# Motor_Drivers.net
KiCad netlist of a schematic drawn in Altium Designer
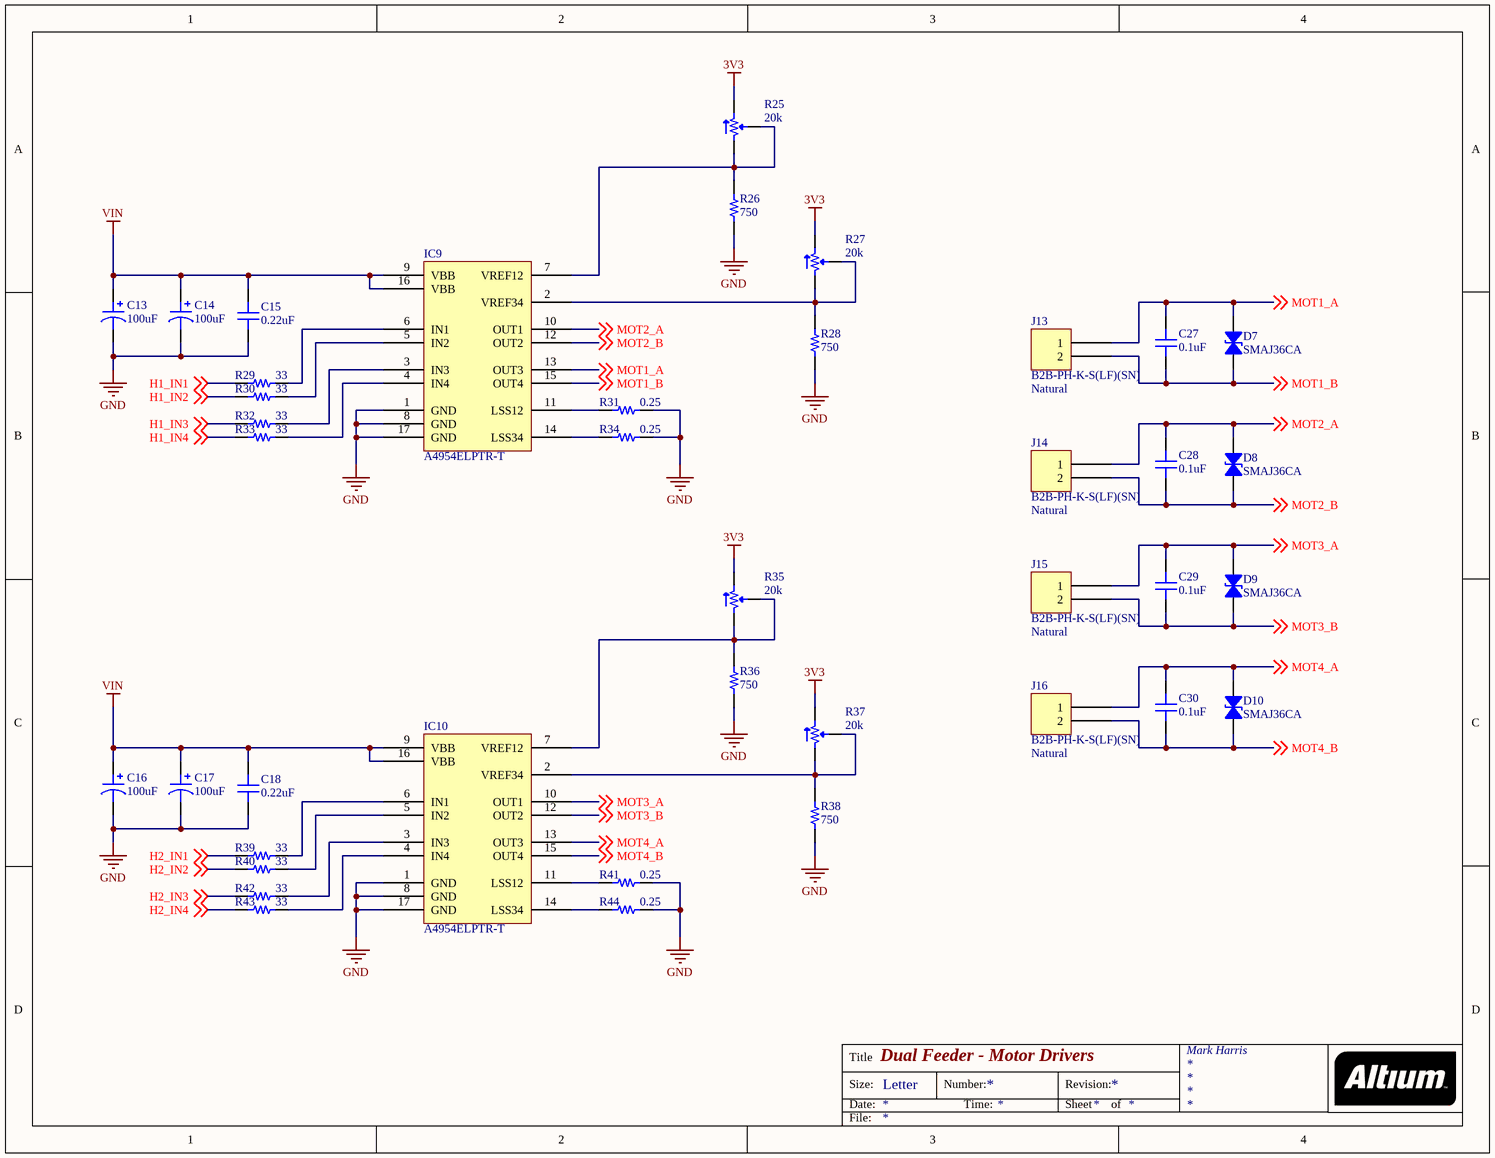
[diagram p0: Motor Drivers.SchDoc]

(export (version "E")
  (design (tool "Eeschema 10.0.6"))
  (components
    (comp (ref "C13")
      (value "100uF")
      (footprint "CAP ALUM 8.3MM")
      (description "CAP ALUM 100UF 20% 50V SMD")
      (fields (field (name "PART NUMBER") "UWT1H101MNL1GS") (field (name "MANUFACTURER") "Nichicon"))
      (libsource (lib "Celestial Library Database") (part "Polarised Capacitor"))
    )
    (comp (ref "C14")
      (value "100uF")
      (footprint "CAP ALUM 8.3MM")
      (description "CAP ALUM 100UF 20% 50V SMD")
      (fields (field (name "PART NUMBER") "UWT1H101MNL1GS") (field (name "MANUFACTURER") "Nichicon"))
      (libsource (lib "Celestial Library Database") (part "Polarised Capacitor"))
    )
    (comp (ref "C15")
      (value "0.22uF")
      (footprint "CAP 0805/2012")
      (description "CAP CER 0.22UF 50V X7R 0805")
      (fields
        (field (name "PART NUMBER") "CL21B224KBFSFNE")
        (field (name "MANUFACTURER") "Samsung Electro-Mechanics America, Inc.")
      )
      (libsource (lib "Celestial Library Database") (part "Capacitor"))
    )
    (comp (ref "C16")
      (value "100uF")
      (footprint "CAP ALUM 8.3MM")
      (description "CAP ALUM 100UF 20% 50V SMD")
      (fields (field (name "PART NUMBER") "UWT1H101MNL1GS") (field (name "MANUFACTURER") "Nichicon"))
      (libsource (lib "Celestial Library Database") (part "Polarised Capacitor"))
    )
    (comp (ref "C17")
      (value "100uF")
      (footprint "CAP ALUM 8.3MM")
      (description "CAP ALUM 100UF 20% 50V SMD")
      (fields (field (name "PART NUMBER") "UWT1H101MNL1GS") (field (name "MANUFACTURER") "Nichicon"))
      (libsource (lib "Celestial Library Database") (part "Polarised Capacitor"))
    )
    (comp (ref "C18")
      (value "0.22uF")
      (footprint "CAP 0805/2012")
      (description "CAP CER 0.22UF 50V X7R 0805")
      (fields
        (field (name "PART NUMBER") "CL21B224KBFSFNE")
        (field (name "MANUFACTURER") "Samsung Electro-Mechanics America, Inc.")
      )
      (libsource (lib "Celestial Library Database") (part "Capacitor"))
    )
    (comp (ref "C27")
      (value "0.1uF")
      (footprint "CAP 0603/1608")
      (description "CAP CER 0.1UF 50V X7R 0603")
      (fields
        (field (name "PART NUMBER") "CL10B104JB8NNNC")
        (field (name "MANUFACTURER") "Samsung Electro-Mechanics America, Inc.")
      )
      (libsource (lib "Celestial Library Database") (part "Capacitor"))
    )
    (comp (ref "C28")
      (value "0.1uF")
      (footprint "CAP 0603/1608")
      (description "CAP CER 0.1UF 50V X7R 0603")
      (fields
        (field (name "PART NUMBER") "CL10B104JB8NNNC")
        (field (name "MANUFACTURER") "Samsung Electro-Mechanics America, Inc.")
      )
      (libsource (lib "Celestial Library Database") (part "Capacitor"))
    )
    (comp (ref "C29")
      (value "0.1uF")
      (footprint "CAP 0603/1608")
      (description "CAP CER 0.1UF 50V X7R 0603")
      (fields
        (field (name "PART NUMBER") "CL10B104JB8NNNC")
        (field (name "MANUFACTURER") "Samsung Electro-Mechanics America, Inc.")
      )
      (libsource (lib "Celestial Library Database") (part "Capacitor"))
    )
    (comp (ref "C30")
      (value "0.1uF")
      (footprint "CAP 0603/1608")
      (description "CAP CER 0.1UF 50V X7R 0603")
      (fields
        (field (name "PART NUMBER") "CL10B104JB8NNNC")
        (field (name "MANUFACTURER") "Samsung Electro-Mechanics America, Inc.")
      )
      (libsource (lib "Celestial Library Database") (part "Capacitor"))
    )
    (comp (ref "D7")
      (value "SMAJ36CA")
      (footprint "Bourns DO214AC SMA")
      (description "TVS DIODE 36VWM 58.1VC DO214AC")
      (fields (field (name "MANUFACTURER") "Bourns Inc."))
      (libsource (lib "Celestial Library Database") (part "Diode Zener Bidirectional"))
    )
    (comp (ref "D8")
      (value "SMAJ36CA")
      (footprint "Bourns DO214AC SMA")
      (description "TVS DIODE 36VWM 58.1VC DO214AC")
      (fields (field (name "MANUFACTURER") "Bourns Inc."))
      (libsource (lib "Celestial Library Database") (part "Diode Zener Bidirectional"))
    )
    (comp (ref "D9")
      (value "SMAJ36CA")
      (footprint "Bourns DO214AC SMA")
      (description "TVS DIODE 36VWM 58.1VC DO214AC")
      (fields (field (name "MANUFACTURER") "Bourns Inc."))
      (libsource (lib "Celestial Library Database") (part "Diode Zener Bidirectional"))
    )
    (comp (ref "D10")
      (value "SMAJ36CA")
      (footprint "Bourns DO214AC SMA")
      (description "TVS DIODE 36VWM 58.1VC DO214AC")
      (fields (field (name "MANUFACTURER") "Bourns Inc."))
      (libsource (lib "Celestial Library Database") (part "Diode Zener Bidirectional"))
    )
    (comp (ref "IC9")
      (value "A4954ELPTR-T")
      (footprint "ALLEGRO TSSOP-16EP LP")
      (description "IC MOTOR DRIVER PAR 16TSSOP")
      (fields (field (name "MANUFACTURER") "Allegro MicroSystems, LLC"))
      (libsource (lib "Celestial Library Database") (part "Allegro A4954"))
    )
    (comp (ref "IC10")
      (value "A4954ELPTR-T")
      (footprint "ALLEGRO TSSOP-16EP LP")
      (description "IC MOTOR DRIVER PAR 16TSSOP")
      (fields (field (name "MANUFACTURER") "Allegro MicroSystems, LLC"))
      (libsource (lib "Celestial Library Database") (part "Allegro A4954"))
    )
    (comp (ref "J13")
      (value "B2B-PH-K-S(LF)(SN)")
      (footprint "JST B2B-PH-K")
      (description "CONN HEADER PH TOP 2POS 2MM")
      (fields (field (name "COLOUR") "Natural") (field (name "MANUFACTURER") "JST Sales America Inc."))
      (libsource (lib "Celestial Library Database") (part "2 Pin"))
    )
    (comp (ref "J14")
      (value "B2B-PH-K-S(LF)(SN)")
      (footprint "JST B2B-PH-K")
      (description "CONN HEADER PH TOP 2POS 2MM")
      (fields (field (name "COLOUR") "Natural") (field (name "MANUFACTURER") "JST Sales America Inc."))
      (libsource (lib "Celestial Library Database") (part "2 Pin"))
    )
    (comp (ref "J15")
      (value "B2B-PH-K-S(LF)(SN)")
      (footprint "JST B2B-PH-K")
      (description "CONN HEADER PH TOP 2POS 2MM")
      (fields (field (name "COLOUR") "Natural") (field (name "MANUFACTURER") "JST Sales America Inc."))
      (libsource (lib "Celestial Library Database") (part "2 Pin"))
    )
    (comp (ref "J16")
      (value "B2B-PH-K-S(LF)(SN)")
      (footprint "JST B2B-PH-K")
      (description "CONN HEADER PH TOP 2POS 2MM")
      (fields (field (name "COLOUR") "Natural") (field (name "MANUFACTURER") "JST Sales America Inc."))
      (libsource (lib "Celestial Library Database") (part "2 Pin"))
    )
    (comp (ref "R25")
      (value "20k")
      (footprint "POT BOURNS TRIMPOT 3302")
      (description "TRIMMER 20K OHM 0.15W SMD")
      (fields (field (name "PART NUMBER") "3302W-3-203E") (field (name "MANUFACTURER") "Bourns Inc."))
      (libsource (lib "Celestial Library Database") (part "Potentiometer"))
    )
    (comp (ref "R26")
      (value "750")
      (footprint "RES 0603/1608")
      (description "RES SMD 750 OHM 1% 1/10W 0603")
      (fields
        (field (name "PART NUMBER") "ERJ-3EKF7500V")
        (field (name "MANUFACTURER") "Panasonic Electronic Components")
      )
      (libsource (lib "Celestial Library Database") (part "Resistor"))
    )
    (comp (ref "R27")
      (value "20k")
      (footprint "POT BOURNS TRIMPOT 3302")
      (description "TRIMMER 20K OHM 0.15W SMD")
      (fields (field (name "PART NUMBER") "3302W-3-203E") (field (name "MANUFACTURER") "Bourns Inc."))
      (libsource (lib "Celestial Library Database") (part "Potentiometer"))
    )
    (comp (ref "R28")
      (value "750")
      (footprint "RES 0603/1608")
      (description "RES SMD 750 OHM 1% 1/10W 0603")
      (fields
        (field (name "PART NUMBER") "ERJ-3EKF7500V")
        (field (name "MANUFACTURER") "Panasonic Electronic Components")
      )
      (libsource (lib "Celestial Library Database") (part "Resistor"))
    )
    (comp (ref "R29")
      (value "33")
      (footprint "RES 0603/1608")
      (description "RES SMD 33 OHM 1% 1/10W 0603")
      (fields
        (field (name "PART NUMBER") "ERJ-3EKF33R0V")
        (field (name "MANUFACTURER") "Panasonic Electronic Components")
      )
      (libsource (lib "Celestial Library Database") (part "Resistor"))
    )
    (comp (ref "R30")
      (value "33")
      (footprint "RES 0603/1608")
      (description "RES SMD 33 OHM 1% 1/10W 0603")
      (fields
        (field (name "PART NUMBER") "ERJ-3EKF33R0V")
        (field (name "MANUFACTURER") "Panasonic Electronic Components")
      )
      (libsource (lib "Celestial Library Database") (part "Resistor"))
    )
    (comp (ref "R31")
      (value "0.25")
      (footprint "STACKPOLE CSR1206")
      (description "RES SMD 0.25 OHM 1% 1/2W 1206")
      (fields
        (field (name "PART NUMBER") "CSR1206FKR250")
        (field (name "MANUFACTURER") "Stackpole Electronics Inc.")
      )
      (libsource (lib "Celestial Library Database") (part "Resistor"))
    )
    (comp (ref "R32")
      (value "33")
      (footprint "RES 0603/1608")
      (description "RES SMD 33 OHM 1% 1/10W 0603")
      (fields
        (field (name "PART NUMBER") "ERJ-3EKF33R0V")
        (field (name "MANUFACTURER") "Panasonic Electronic Components")
      )
      (libsource (lib "Celestial Library Database") (part "Resistor"))
    )
    (comp (ref "R33")
      (value "33")
      (footprint "RES 0603/1608")
      (description "RES SMD 33 OHM 1% 1/10W 0603")
      (fields
        (field (name "PART NUMBER") "ERJ-3EKF33R0V")
        (field (name "MANUFACTURER") "Panasonic Electronic Components")
      )
      (libsource (lib "Celestial Library Database") (part "Resistor"))
    )
    (comp (ref "R34")
      (value "0.25")
      (footprint "STACKPOLE CSR1206")
      (description "RES SMD 0.25 OHM 1% 1/2W 1206")
      (fields
        (field (name "PART NUMBER") "CSR1206FKR250")
        (field (name "MANUFACTURER") "Stackpole Electronics Inc.")
      )
      (libsource (lib "Celestial Library Database") (part "Resistor"))
    )
    (comp (ref "R35")
      (value "20k")
      (footprint "POT BOURNS TRIMPOT 3302")
      (description "TRIMMER 20K OHM 0.15W SMD")
      (fields (field (name "PART NUMBER") "3302W-3-203E") (field (name "MANUFACTURER") "Bourns Inc."))
      (libsource (lib "Celestial Library Database") (part "Potentiometer"))
    )
    (comp (ref "R36")
      (value "750")
      (footprint "RES 0603/1608")
      (description "RES SMD 750 OHM 1% 1/10W 0603")
      (fields
        (field (name "PART NUMBER") "ERJ-3EKF7500V")
        (field (name "MANUFACTURER") "Panasonic Electronic Components")
      )
      (libsource (lib "Celestial Library Database") (part "Resistor"))
    )
    (comp (ref "R37")
      (value "20k")
      (footprint "POT BOURNS TRIMPOT 3302")
      (description "TRIMMER 20K OHM 0.15W SMD")
      (fields (field (name "PART NUMBER") "3302W-3-203E") (field (name "MANUFACTURER") "Bourns Inc."))
      (libsource (lib "Celestial Library Database") (part "Potentiometer"))
    )
    (comp (ref "R38")
      (value "750")
      (footprint "RES 0603/1608")
      (description "RES SMD 750 OHM 1% 1/10W 0603")
      (fields
        (field (name "PART NUMBER") "ERJ-3EKF7500V")
        (field (name "MANUFACTURER") "Panasonic Electronic Components")
      )
      (libsource (lib "Celestial Library Database") (part "Resistor"))
    )
    (comp (ref "R39")
      (value "33")
      (footprint "RES 0603/1608")
      (description "RES SMD 33 OHM 1% 1/10W 0603")
      (fields
        (field (name "PART NUMBER") "ERJ-3EKF33R0V")
        (field (name "MANUFACTURER") "Panasonic Electronic Components")
      )
      (libsource (lib "Celestial Library Database") (part "Resistor"))
    )
    (comp (ref "R40")
      (value "33")
      (footprint "RES 0603/1608")
      (description "RES SMD 33 OHM 1% 1/10W 0603")
      (fields
        (field (name "PART NUMBER") "ERJ-3EKF33R0V")
        (field (name "MANUFACTURER") "Panasonic Electronic Components")
      )
      (libsource (lib "Celestial Library Database") (part "Resistor"))
    )
    (comp (ref "R41")
      (value "0.25")
      (footprint "STACKPOLE CSR1206")
      (description "RES SMD 0.25 OHM 1% 1/2W 1206")
      (fields
        (field (name "PART NUMBER") "CSR1206FKR250")
        (field (name "MANUFACTURER") "Stackpole Electronics Inc.")
      )
      (libsource (lib "Celestial Library Database") (part "Resistor"))
    )
    (comp (ref "R42")
      (value "33")
      (footprint "RES 0603/1608")
      (description "RES SMD 33 OHM 1% 1/10W 0603")
      (fields
        (field (name "PART NUMBER") "ERJ-3EKF33R0V")
        (field (name "MANUFACTURER") "Panasonic Electronic Components")
      )
      (libsource (lib "Celestial Library Database") (part "Resistor"))
    )
    (comp (ref "R43")
      (value "33")
      (footprint "RES 0603/1608")
      (description "RES SMD 33 OHM 1% 1/10W 0603")
      (fields
        (field (name "PART NUMBER") "ERJ-3EKF33R0V")
        (field (name "MANUFACTURER") "Panasonic Electronic Components")
      )
      (libsource (lib "Celestial Library Database") (part "Resistor"))
    )
    (comp (ref "R44")
      (value "0.25")
      (footprint "STACKPOLE CSR1206")
      (description "RES SMD 0.25 OHM 1% 1/2W 1206")
      (fields
        (field (name "PART NUMBER") "CSR1206FKR250")
        (field (name "MANUFACTURER") "Stackpole Electronics Inc.")
      )
      (libsource (lib "Celestial Library Database") (part "Resistor"))
    )
  )
  (nets
    (net (code "1") (name "3V3") (class "Default")
      (node (ref "R25") (pin "3") (pinfunction "3_3") (pintype "passive"))
      (node (ref "R27") (pin "3") (pinfunction "3_3") (pintype "passive"))
      (node (ref "R35") (pin "3") (pinfunction "3_3") (pintype "passive"))
      (node (ref "R37") (pin "3") (pinfunction "3_3") (pintype "passive"))
    )
    (net (code "2") (name "GND") (class "Default")
      (node (ref "C13") (pin "2") (pinfunction "2_2") (pintype "passive"))
      (node (ref "C14") (pin "2") (pinfunction "2_2") (pintype "passive"))
      (node (ref "C15") (pin "1") (pinfunction "1_1") (pintype "passive"))
      (node (ref "C16") (pin "2") (pinfunction "2_2") (pintype "passive"))
      (node (ref "C17") (pin "2") (pinfunction "2_2") (pintype "passive"))
      (node (ref "C18") (pin "1") (pinfunction "1_1") (pintype "passive"))
      (node (ref "IC10") (pin "1") (pinfunction "GND_1") (pintype "passive"))
      (node (ref "IC10") (pin "17") (pinfunction "GND_17") (pintype "passive"))
      (node (ref "IC10") (pin "8") (pinfunction "GND_8") (pintype "passive"))
      (node (ref "IC9") (pin "1") (pinfunction "GND_1") (pintype "passive"))
      (node (ref "IC9") (pin "17") (pinfunction "GND_17") (pintype "passive"))
      (node (ref "IC9") (pin "8") (pinfunction "GND_8") (pintype "passive"))
      (node (ref "R26") (pin "1") (pinfunction "1_1") (pintype "passive"))
      (node (ref "R28") (pin "1") (pinfunction "1_1") (pintype "passive"))
      (node (ref "R31") (pin "2") (pinfunction "2_2") (pintype "passive"))
      (node (ref "R34") (pin "2") (pinfunction "2_2") (pintype "passive"))
      (node (ref "R36") (pin "1") (pinfunction "1_1") (pintype "passive"))
      (node (ref "R38") (pin "1") (pinfunction "1_1") (pintype "passive"))
      (node (ref "R41") (pin "2") (pinfunction "2_2") (pintype "passive"))
      (node (ref "R44") (pin "2") (pinfunction "2_2") (pintype "passive"))
    )
    (net (code "3") (name "H1_IN1") (class "Default")
      (node (ref "R29") (pin "1") (pinfunction "1_1") (pintype "passive"))
    )
    (net (code "4") (name "H1_IN2") (class "Default")
      (node (ref "R30") (pin "1") (pinfunction "1_1") (pintype "passive"))
    )
    (net (code "5") (name "H1_IN3") (class "Default")
      (node (ref "R32") (pin "1") (pinfunction "1_1") (pintype "passive"))
    )
    (net (code "6") (name "H1_IN4") (class "Default")
      (node (ref "R33") (pin "1") (pinfunction "1_1") (pintype "passive"))
    )
    (net (code "7") (name "H2_IN1") (class "Default")
      (node (ref "R39") (pin "1") (pinfunction "1_1") (pintype "passive"))
    )
    (net (code "8") (name "H2_IN2") (class "Default")
      (node (ref "R40") (pin "1") (pinfunction "1_1") (pintype "passive"))
    )
    (net (code "9") (name "H2_IN3") (class "Default")
      (node (ref "R42") (pin "1") (pinfunction "1_1") (pintype "passive"))
    )
    (net (code "10") (name "H2_IN4") (class "Default")
      (node (ref "R43") (pin "1") (pinfunction "1_1") (pintype "passive"))
    )
    (net (code "11") (name "MOT1_A") (class "Default")
      (node (ref "C27") (pin "1") (pinfunction "1_1") (pintype "passive"))
      (node (ref "D7") (pin "2") (pinfunction "2_2") (pintype "passive"))
      (node (ref "IC9") (pin "13") (pinfunction "OUT3_13") (pintype "passive"))
      (node (ref "J13") (pin "1") (pinfunction "1_1") (pintype "passive"))
    )
    (net (code "12") (name "MOT1_B") (class "Default")
      (node (ref "C27") (pin "2") (pinfunction "2_2") (pintype "passive"))
      (node (ref "D7") (pin "1") (pinfunction "1_1") (pintype "passive"))
      (node (ref "IC9") (pin "15") (pinfunction "OUT4_15") (pintype "passive"))
      (node (ref "J13") (pin "2") (pinfunction "2_2") (pintype "passive"))
    )
    (net (code "13") (name "MOT2_A") (class "Default")
      (node (ref "C28") (pin "1") (pinfunction "1_1") (pintype "passive"))
      (node (ref "D8") (pin "2") (pinfunction "2_2") (pintype "passive"))
      (node (ref "IC9") (pin "10") (pinfunction "OUT1_10") (pintype "passive"))
      (node (ref "J14") (pin "1") (pinfunction "1_1") (pintype "passive"))
    )
    (net (code "14") (name "MOT2_B") (class "Default")
      (node (ref "C28") (pin "2") (pinfunction "2_2") (pintype "passive"))
      (node (ref "D8") (pin "1") (pinfunction "1_1") (pintype "passive"))
      (node (ref "IC9") (pin "12") (pinfunction "OUT2_12") (pintype "passive"))
      (node (ref "J14") (pin "2") (pinfunction "2_2") (pintype "passive"))
    )
    (net (code "15") (name "MOT3_A") (class "Default")
      (node (ref "C29") (pin "1") (pinfunction "1_1") (pintype "passive"))
      (node (ref "D9") (pin "2") (pinfunction "2_2") (pintype "passive"))
      (node (ref "IC10") (pin "10") (pinfunction "OUT1_10") (pintype "passive"))
      (node (ref "J15") (pin "1") (pinfunction "1_1") (pintype "passive"))
    )
    (net (code "16") (name "MOT3_B") (class "Default")
      (node (ref "C29") (pin "2") (pinfunction "2_2") (pintype "passive"))
      (node (ref "D9") (pin "1") (pinfunction "1_1") (pintype "passive"))
      (node (ref "IC10") (pin "12") (pinfunction "OUT2_12") (pintype "passive"))
      (node (ref "J15") (pin "2") (pinfunction "2_2") (pintype "passive"))
    )
    (net (code "17") (name "MOT4_A") (class "Default")
      (node (ref "C30") (pin "1") (pinfunction "1_1") (pintype "passive"))
      (node (ref "D10") (pin "2") (pinfunction "2_2") (pintype "passive"))
      (node (ref "IC10") (pin "13") (pinfunction "OUT3_13") (pintype "passive"))
      (node (ref "J16") (pin "1") (pinfunction "1_1") (pintype "passive"))
    )
    (net (code "18") (name "MOT4_B") (class "Default")
      (node (ref "C30") (pin "2") (pinfunction "2_2") (pintype "passive"))
      (node (ref "D10") (pin "1") (pinfunction "1_1") (pintype "passive"))
      (node (ref "IC10") (pin "15") (pinfunction "OUT4_15") (pintype "passive"))
      (node (ref "J16") (pin "2") (pinfunction "2_2") (pintype "passive"))
    )
    (net (code "19") (name "Net-(IC9-IN1)") (class "Default")
      (node (ref "IC9") (pin "6") (pinfunction "IN1_6") (pintype "passive"))
      (node (ref "R29") (pin "2") (pinfunction "2_2") (pintype "passive"))
    )
    (net (code "20") (name "Net-(IC9-IN2)") (class "Default")
      (node (ref "IC9") (pin "5") (pinfunction "IN2_5") (pintype "passive"))
      (node (ref "R30") (pin "2") (pinfunction "2_2") (pintype "passive"))
    )
    (net (code "21") (name "Net-(IC9-IN3)") (class "Default")
      (node (ref "IC9") (pin "3") (pinfunction "IN3_3") (pintype "passive"))
      (node (ref "R32") (pin "2") (pinfunction "2_2") (pintype "passive"))
    )
    (net (code "22") (name "Net-(IC9-IN4)") (class "Default")
      (node (ref "IC9") (pin "4") (pinfunction "IN4_4") (pintype "passive"))
      (node (ref "R33") (pin "2") (pinfunction "2_2") (pintype "passive"))
    )
    (net (code "23") (name "Net-(IC9-LSS12)") (class "Default")
      (node (ref "IC9") (pin "11") (pinfunction "LSS12_11") (pintype "passive"))
      (node (ref "R31") (pin "1") (pinfunction "1_1") (pintype "passive"))
    )
    (net (code "24") (name "Net-(IC9-LSS34)") (class "Default")
      (node (ref "IC9") (pin "14") (pinfunction "LSS34_14") (pintype "passive"))
      (node (ref "R34") (pin "1") (pinfunction "1_1") (pintype "passive"))
    )
    (net (code "25") (name "Net-(IC9-VREF12)") (class "Default")
      (node (ref "IC9") (pin "7") (pinfunction "VREF12_7") (pintype "passive"))
      (node (ref "R25") (pin "1") (pinfunction "1_1") (pintype "passive"))
      (node (ref "R25") (pin "2") (pinfunction "2_2") (pintype "passive"))
      (node (ref "R26") (pin "2") (pinfunction "2_2") (pintype "passive"))
    )
    (net (code "26") (name "Net-(IC9-VREF34)") (class "Default")
      (node (ref "IC9") (pin "2") (pinfunction "VREF34_2") (pintype "passive"))
      (node (ref "R27") (pin "1") (pinfunction "1_1") (pintype "passive"))
      (node (ref "R27") (pin "2") (pinfunction "2_2") (pintype "passive"))
      (node (ref "R28") (pin "2") (pinfunction "2_2") (pintype "passive"))
    )
    (net (code "27") (name "Net-(IC10-IN1)") (class "Default")
      (node (ref "IC10") (pin "6") (pinfunction "IN1_6") (pintype "passive"))
      (node (ref "R39") (pin "2") (pinfunction "2_2") (pintype "passive"))
    )
    (net (code "28") (name "Net-(IC10-IN2)") (class "Default")
      (node (ref "IC10") (pin "5") (pinfunction "IN2_5") (pintype "passive"))
      (node (ref "R40") (pin "2") (pinfunction "2_2") (pintype "passive"))
    )
    (net (code "29") (name "Net-(IC10-IN3)") (class "Default")
      (node (ref "IC10") (pin "3") (pinfunction "IN3_3") (pintype "passive"))
      (node (ref "R42") (pin "2") (pinfunction "2_2") (pintype "passive"))
    )
    (net (code "30") (name "Net-(IC10-IN4)") (class "Default")
      (node (ref "IC10") (pin "4") (pinfunction "IN4_4") (pintype "passive"))
      (node (ref "R43") (pin "2") (pinfunction "2_2") (pintype "passive"))
    )
    (net (code "31") (name "Net-(IC10-LSS12)") (class "Default")
      (node (ref "IC10") (pin "11") (pinfunction "LSS12_11") (pintype "passive"))
      (node (ref "R41") (pin "1") (pinfunction "1_1") (pintype "passive"))
    )
    (net (code "32") (name "Net-(IC10-LSS34)") (class "Default")
      (node (ref "IC10") (pin "14") (pinfunction "LSS34_14") (pintype "passive"))
      (node (ref "R44") (pin "1") (pinfunction "1_1") (pintype "passive"))
    )
    (net (code "33") (name "Net-(IC10-VREF12)") (class "Default")
      (node (ref "IC10") (pin "7") (pinfunction "VREF12_7") (pintype "passive"))
      (node (ref "R35") (pin "1") (pinfunction "1_1") (pintype "passive"))
      (node (ref "R35") (pin "2") (pinfunction "2_2") (pintype "passive"))
      (node (ref "R36") (pin "2") (pinfunction "2_2") (pintype "passive"))
    )
    (net (code "34") (name "Net-(IC10-VREF34)") (class "Default")
      (node (ref "IC10") (pin "2") (pinfunction "VREF34_2") (pintype "passive"))
      (node (ref "R37") (pin "1") (pinfunction "1_1") (pintype "passive"))
      (node (ref "R37") (pin "2") (pinfunction "2_2") (pintype "passive"))
      (node (ref "R38") (pin "2") (pinfunction "2_2") (pintype "passive"))
    )
    (net (code "35") (name "VIN") (class "Default")
      (node (ref "C13") (pin "1") (pinfunction "1_1") (pintype "passive"))
      (node (ref "C14") (pin "1") (pinfunction "1_1") (pintype "passive"))
      (node (ref "C15") (pin "2") (pinfunction "2_2") (pintype "passive"))
      (node (ref "C16") (pin "1") (pinfunction "1_1") (pintype "passive"))
      (node (ref "C17") (pin "1") (pinfunction "1_1") (pintype "passive"))
      (node (ref "C18") (pin "2") (pinfunction "2_2") (pintype "passive"))
      (node (ref "IC10") (pin "16") (pinfunction "VBB_16") (pintype "passive"))
      (node (ref "IC10") (pin "9") (pinfunction "VBB_9") (pintype "passive"))
      (node (ref "IC9") (pin "16") (pinfunction "VBB_16") (pintype "passive"))
      (node (ref "IC9") (pin "9") (pinfunction "VBB_9") (pintype "passive"))
    )
  )
)
